# Sheet1.net
KiCad netlist of a schematic drawn in Altium Designer
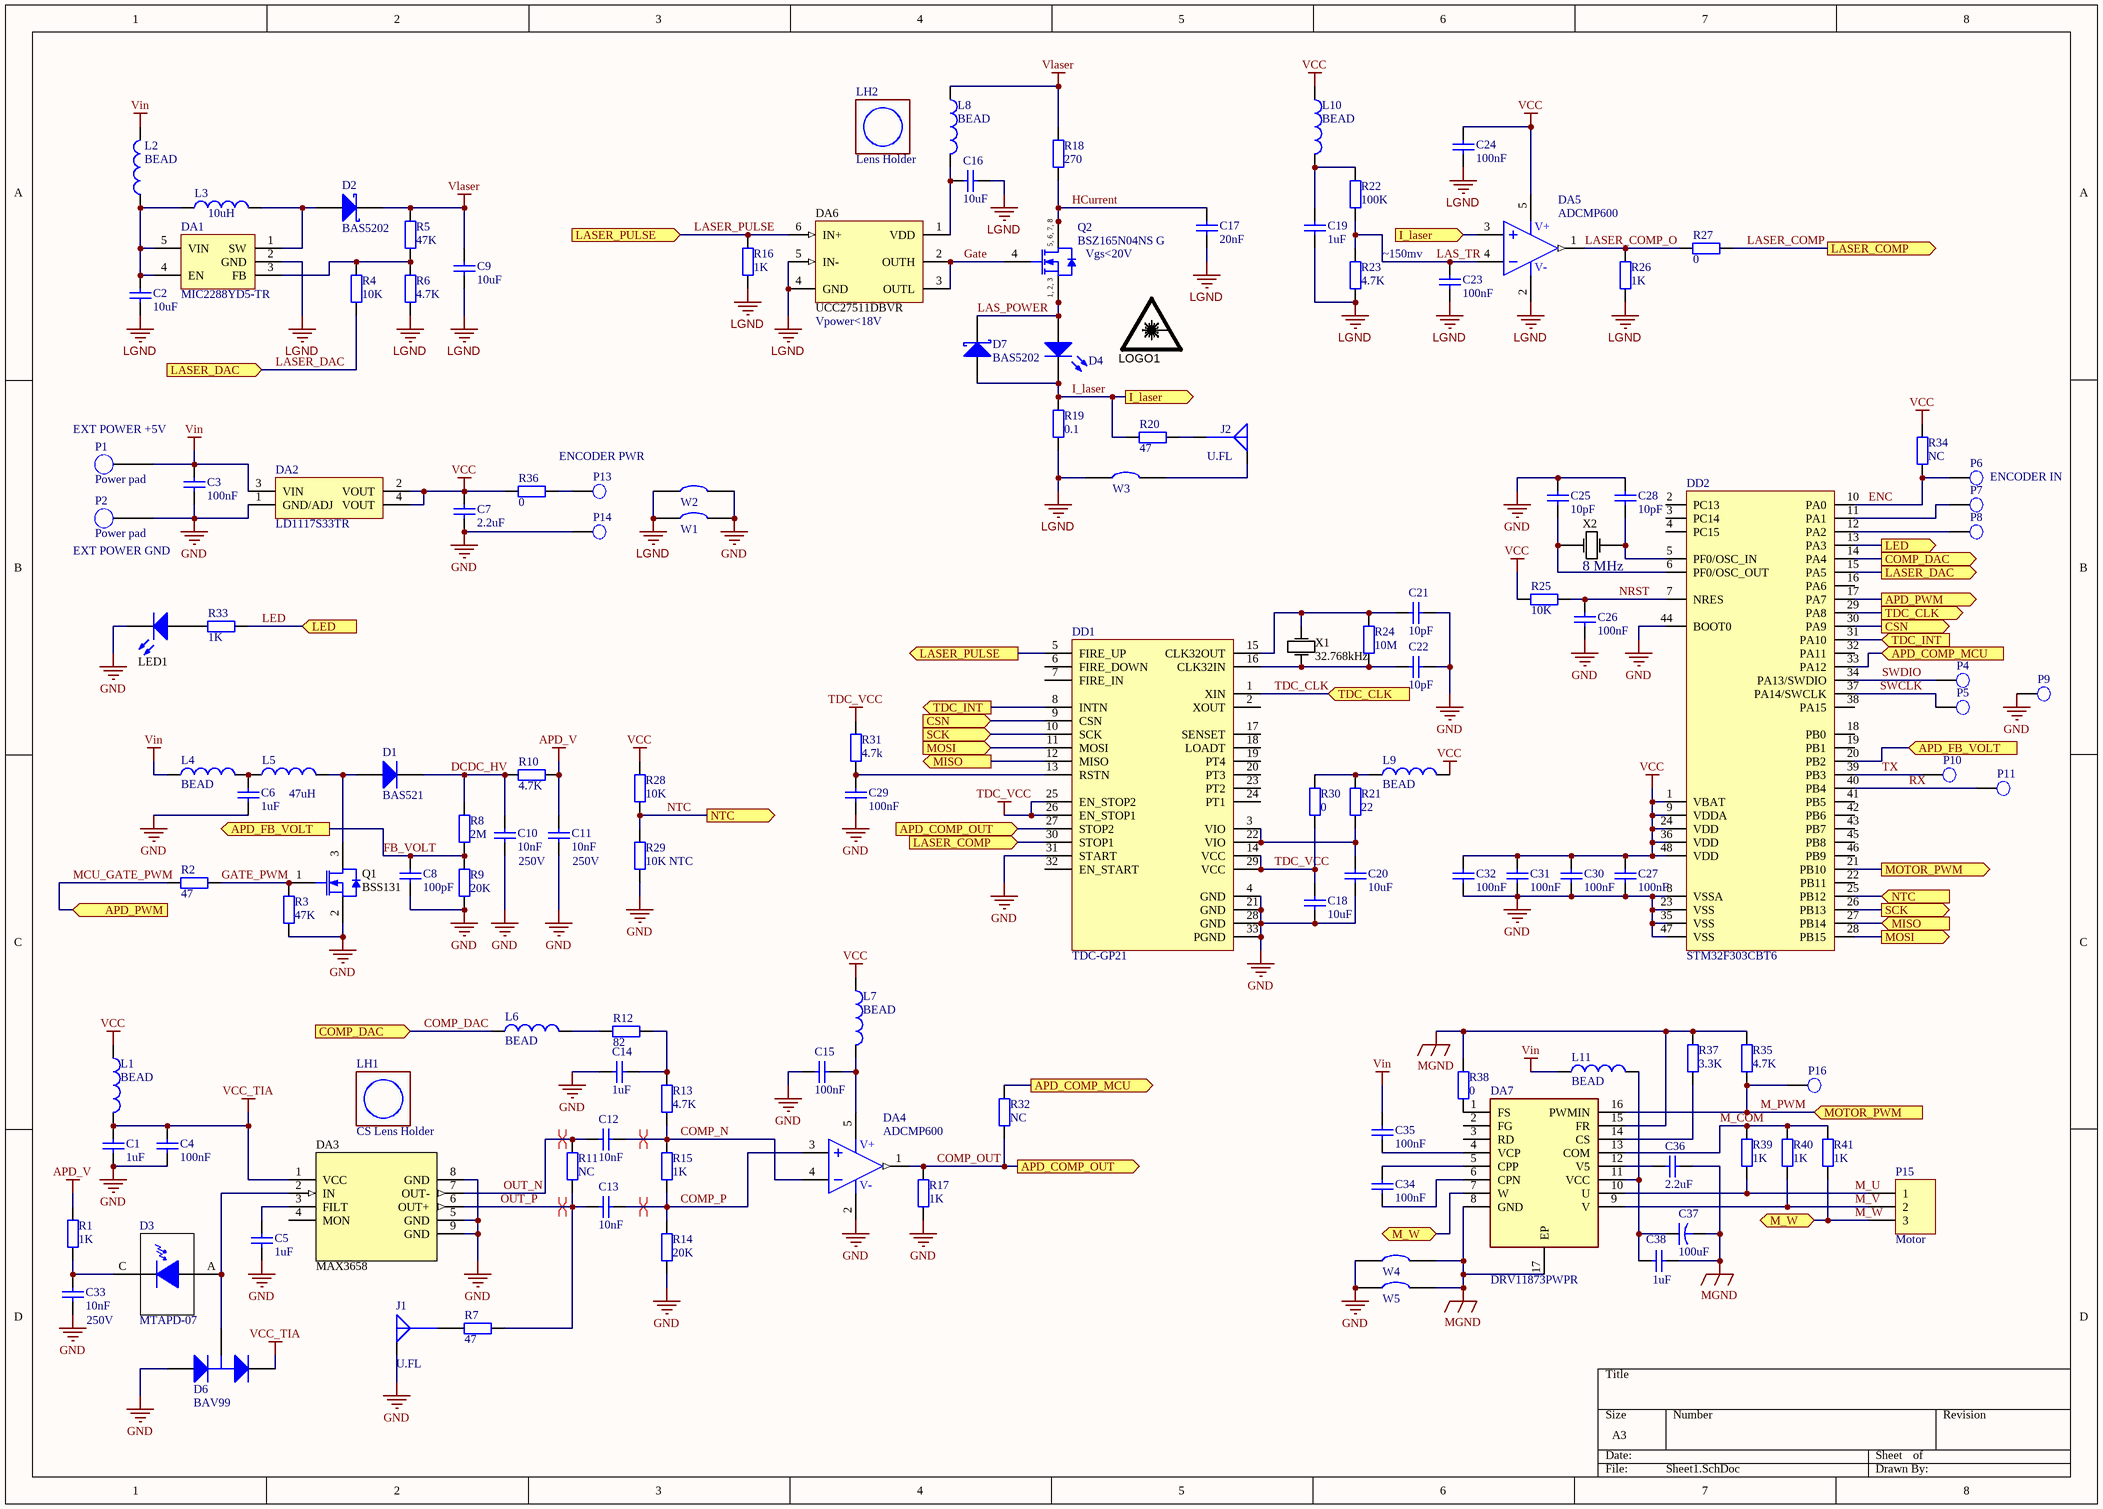
[diagram p0: Sheet1.SchDoc]

(export (version "E")
  (design (tool "Eeschema 10.0.6"))
  (components
    (comp (ref "C1")
      (value "1uF")
      (footprint "CAPC2012X135N")
      (description "Chip capacitor")
      (fields (field (name "VOLTAGE") "25V"))
      (libsource (lib "MyLibSch") (part "CC0805"))
    )
    (comp (ref "C2")
      (value "10uF")
      (footprint "CAPC1608X90N")
      (description "Chip capacitor")
      (fields (field (name "VOLTAGE") "25V"))
      (libsource (lib "MyLibSch") (part "CC0805"))
    )
    (comp (ref "C3")
      (value "100nF")
      (footprint "CAPC1608X90N")
      (description "Chip capacitor")
      (fields (field (name "VOLTAGE") "25V"))
      (libsource (lib "MyLibSch") (part "CC0805"))
    )
    (comp (ref "C4")
      (value "100nF")
      (footprint "CAPC1608X90N")
      (description "Chip capacitor")
      (fields (field (name "VOLTAGE") "25V"))
      (libsource (lib "MyLibSch") (part "CC0805"))
    )
    (comp (ref "C5")
      (value "1uF")
      (footprint "CAPC2012X135N")
      (description "Chip capacitor")
      (fields (field (name "VOLTAGE") "25V"))
      (libsource (lib "MyLibSch") (part "CC0805"))
    )
    (comp (ref "C6")
      (value "1uF")
      (footprint "CAPC2012X135N")
      (description "Chip capacitor")
      (fields (field (name "VOLTAGE") "25V"))
      (libsource (lib "MyLibSch") (part "CC0805"))
    )
    (comp (ref "C7")
      (value "2.2uF")
      (footprint "CAPC1608X90N")
      (description "Chip capacitor")
      (fields (field (name "VOLTAGE") "25V"))
      (libsource (lib "MyLibSch") (part "CC0805"))
    )
    (comp (ref "C8")
      (value "100pF")
      (footprint "CAPC1608X90N")
      (description "Chip capacitor")
      (fields (field (name "VOLTAGE") "25V"))
      (libsource (lib "MyLibSch") (part "CC0805"))
    )
    (comp (ref "C9")
      (value "10uF")
      (footprint "CAPC1608X90N")
      (description "Chip capacitor")
      (fields (field (name "VOLTAGE") "50V"))
      (libsource (lib "MyLibSch") (part "CC0805"))
    )
    (comp (ref "C10")
      (value "10nF")
      (footprint "CAPC2012X135N")
      (description "Chip capacitor")
      (fields (field (name "VOLTAGE") "250V"))
      (libsource (lib "MyLibSch") (part "CC0805"))
    )
    (comp (ref "C11")
      (value "10nF")
      (footprint "CAPC2012X135N")
      (description "Chip capacitor")
      (fields (field (name "VOLTAGE") "250V"))
      (libsource (lib "MyLibSch") (part "CC0805"))
    )
    (comp (ref "C12")
      (value "10nF")
      (footprint "CAPC1608X90N")
      (description "Chip capacitor")
      (fields (field (name "VOLTAGE") "25V"))
      (libsource (lib "MyLibSch") (part "CC0805"))
    )
    (comp (ref "C13")
      (value "10nF")
      (footprint "CAPC1608X90N")
      (description "Chip capacitor")
      (fields (field (name "VOLTAGE") "25V"))
      (libsource (lib "MyLibSch") (part "CC0805"))
    )
    (comp (ref "C14")
      (value "1uF")
      (footprint "CAPC2012X135N")
      (description "Chip capacitor")
      (fields (field (name "VOLTAGE") "25V"))
      (libsource (lib "MyLibSch") (part "CC0805"))
    )
    (comp (ref "C15")
      (value "100nF")
      (footprint "CAPC1608X90N")
      (description "Chip capacitor")
      (fields (field (name "VOLTAGE") "25V"))
      (libsource (lib "MyLibSch") (part "CC0805"))
    )
    (comp (ref "C16")
      (value "10uF")
      (footprint "CAPC1608X90N")
      (description "Chip capacitor")
      (fields (field (name "VOLTAGE") "25V"))
      (libsource (lib "MyLibSch") (part "CC0805"))
    )
    (comp (ref "C17")
      (value "20nF")
      (footprint "CAPC1608X90N")
      (description "Chip capacitor")
      (fields (field (name "VOLTAGE") "50V"))
      (libsource (lib "MyLibSch") (part "CC0805"))
    )
    (comp (ref "C18")
      (value "10uF")
      (footprint "CAPC1608X90N")
      (description "Chip capacitor")
      (fields (field (name "VOLTAGE") "25V"))
      (libsource (lib "MyLibSch") (part "CC0805"))
    )
    (comp (ref "C19")
      (value "1uF")
      (footprint "CAPC1608X90N")
      (description "Chip capacitor")
      (fields (field (name "VOLTAGE") "25V"))
      (libsource (lib "MyLibSch") (part "CC0805"))
    )
    (comp (ref "C20")
      (value "10uF")
      (footprint "CAPC1608X90N")
      (description "Chip capacitor")
      (fields (field (name "VOLTAGE") "25V"))
      (libsource (lib "MyLibSch") (part "CC0805"))
    )
    (comp (ref "C21")
      (value "10pF")
      (footprint "CAPC1608X90N")
      (description "Chip capacitor")
      (fields (field (name "VOLTAGE") "25V"))
      (libsource (lib "MyLibSch") (part "CC0805"))
    )
    (comp (ref "C22")
      (value "10pF")
      (footprint "CAPC1608X90N")
      (description "Chip capacitor")
      (fields (field (name "VOLTAGE") "25V"))
      (libsource (lib "MyLibSch") (part "CC0805"))
    )
    (comp (ref "C23")
      (value "100nF")
      (footprint "CAPC1608X90N")
      (description "Chip capacitor")
      (fields (field (name "VOLTAGE") "25V"))
      (libsource (lib "MyLibSch") (part "CC0805"))
    )
    (comp (ref "C24")
      (value "100nF")
      (footprint "CAPC1608X90N")
      (description "Chip capacitor")
      (fields (field (name "VOLTAGE") "25V"))
      (libsource (lib "MyLibSch") (part "CC0805"))
    )
    (comp (ref "C25")
      (value "10pF")
      (footprint "CAPC1608X90N")
      (description "Chip capacitor")
      (fields (field (name "VOLTAGE") "25V"))
      (libsource (lib "MyLibSch") (part "CC0805"))
    )
    (comp (ref "C26")
      (value "100nF")
      (footprint "CAPC1608X90N")
      (description "Chip capacitor")
      (fields (field (name "VOLTAGE") "25V"))
      (libsource (lib "MyLibSch") (part "CC0805"))
    )
    (comp (ref "C27")
      (value "100nF")
      (footprint "CAPC1608X90N")
      (description "Chip capacitor")
      (fields (field (name "VOLTAGE") "25V"))
      (libsource (lib "MyLibSch") (part "CC0805"))
    )
    (comp (ref "C28")
      (value "10pF")
      (footprint "CAPC1608X90N")
      (description "Chip capacitor")
      (fields (field (name "VOLTAGE") "25V"))
      (libsource (lib "MyLibSch") (part "CC0805"))
    )
    (comp (ref "C29")
      (value "100nF")
      (footprint "CAPC1608X90N")
      (description "Chip capacitor")
      (fields (field (name "VOLTAGE") "25V"))
      (libsource (lib "MyLibSch") (part "CC0805"))
    )
    (comp (ref "C30")
      (value "100nF")
      (footprint "CAPC1608X90N")
      (description "Chip capacitor")
      (fields (field (name "VOLTAGE") "25V"))
      (libsource (lib "MyLibSch") (part "CC0805"))
    )
    (comp (ref "C31")
      (value "100nF")
      (footprint "CAPC1608X90N")
      (description "Chip capacitor")
      (fields (field (name "VOLTAGE") "25V"))
      (libsource (lib "MyLibSch") (part "CC0805"))
    )
    (comp (ref "C32")
      (value "100nF")
      (footprint "CAPC1608X90N")
      (description "Chip capacitor")
      (fields (field (name "VOLTAGE") "25V"))
      (libsource (lib "MyLibSch") (part "CC0805"))
    )
    (comp (ref "C33")
      (value "10nF")
      (footprint "CAPC2012X135N")
      (description "Chip capacitor")
      (fields (field (name "VOLTAGE") "250V"))
      (libsource (lib "MyLibSch") (part "CC0805"))
    )
    (comp (ref "C34")
      (value "100nF")
      (footprint "CAPC1608X90N")
      (description "Chip capacitor")
      (fields (field (name "VOLTAGE") "25V"))
      (libsource (lib "MyLibSch") (part "CC0805"))
    )
    (comp (ref "C35")
      (value "100nF")
      (footprint "CAPC1608X90N")
      (description "Chip capacitor")
      (fields (field (name "VOLTAGE") "25V"))
      (libsource (lib "MyLibSch") (part "CC0805"))
    )
    (comp (ref "C36")
      (value "2.2uF")
      (footprint "CAPC1608X90N")
      (description "Chip capacitor")
      (fields (field (name "VOLTAGE") "25V"))
      (libsource (lib "MyLibSch") (part "CC0805"))
    )
    (comp (ref "C37")
      (value "100uF")
      (footprint "CAPR5-4X5")
      (description "Capacitor")
      (fields (field (name "Comment") "Cap2") (field (name "PUBLISHER") "Altium Limited"))
      (libsource (lib "Miscellaneous Devices") (part "Cap2"))
    )
    (comp (ref "C38")
      (value "1uF")
      (footprint "CAPC1608X90N")
      (description "Chip capacitor")
      (fields (field (name "VOLTAGE") "25V"))
      (libsource (lib "MyLibSch") (part "CC0805"))
    )
    (comp (ref "D1") (value "BAS521") (footprint "SOD523F") (libsource (lib "MyLibSch") (part "DIODE 2 pin")))
    (comp (ref "D2")
      (value "BAS5202")
      (footprint "SOD523F")
      (description "Schottky Diode")
      (fields (field (name "PUBLISHER") "Altium Limited"))
      (libsource (lib "Miscellaneous Devices") (part "D Schottky"))
    )
    (comp (ref "D3")
      (value "MTAPD-07")
      (footprint "LCC3")
      (description "APD photodiode")
      (libsource (lib "lcd_lib") (part "MTAPD-07"))
    )
    (comp (ref "D4")
      (value "Laser SPL PL90_3")
      (footprint "SPL_PL90")
      (description "TO-18 Laser")
      (libsource (lib "lcd_lib") (part "TO-18 Laser"))
    )
    (comp (ref "D6")
      (value "BAV99")
      (footprint "SOT-23")
      (description "Silicon Switching Diode Array for High-Speed Switching")
      (fields (field (name "PUBLISHER") "Altium Limited"))
      (libsource (lib "Infineon Discrete Diode") (part "BAV99"))
    )
    (comp (ref "D7")
      (value "BAS5202")
      (footprint "SOD523F")
      (description "Schottky Diode")
      (fields (field (name "PUBLISHER") "Altium Limited"))
      (libsource (lib "Miscellaneous Devices") (part "D Schottky"))
    )
    (comp (ref "DA1")
      (value "MIC2288YD5-TR")
      (footprint "SOT23-5")
      (description "Step Up")
      (libsource (lib "lcd_lib") (part "MIC2288"))
    )
    (comp (ref "DA2")
      (value "LD1117S33TR")
      (footprint "SOT223")
      (description "LOW DROP FIXED AND ADJUSTABLE  POSITIVE VOLTAGE REGULATORS")
      (libsource (lib "MyLibSch") (part "LD1117S"))
    )
    (comp (ref "DA3")
      (value "MAX3658")
      (footprint "TDFN-8_0.65")
      (description "Transimpedance Amplifier")
      (fields (field (name "PART NUMBER") "AD7278"))
      (libsource (lib "lcd_lib") (part "MAX3658"))
    )
    (comp (ref "DA4")
      (value "ADCMP600")
      (footprint "SOT23-5")
      (description "Fast comparator")
      (libsource (lib "lcd_lib") (part "ADCMP600"))
    )
    (comp (ref "DA5")
      (value "ADCMP600")
      (footprint "SOT23-5")
      (description "Fast comparator")
      (libsource (lib "lcd_lib") (part "ADCMP600"))
    )
    (comp (ref "DA6")
      (value "UCC27511DBVR")
      (footprint "Miscellaneous Devices:SOT23-6_M")
      (description "Single-Channel High-Speed Low-Side Gate Driver (with 4-A Peak Source and 8-A Peak Sink), DBV0006A")
      (fields
        (field (name "ALTERNATE PARTNUMBER") "UCC27511DBVT")
        (field (name "MANUFACTURER") "Texas Instruments")
        (field (name "SYMBOLCREATOR") "a0411947")
        (field (name "PUBLISHER") "Texas Instruments")
      )
      (libsource (lib "TI_Pre_Release") (part "UCC27511DBVR"))
    )
    (comp (ref "DA7")
      (value "DRV11873PWPR")
      (footprint "SamacSys:SOP65P640X120-17N")
      (description "Integrated Circuit")
      (fields
        (field (name "MOUSER PART NUMBER") "595-DRV11873PWPR")
        (field (name "RS PART NUMBER") "8136444P")
      )
      (libsource (lib "*") (part "DRV11873PWPR"))
    )
    (comp (ref "DD1")
      (value "TDC-GP21")
      (footprint "QFN32 5x5mm")
      (description "TDC")
      (libsource (lib "lcd_lib") (part "TDC_GP21"))
    )
    (comp (ref "DD2")
      (value "STM32F303CBT6")
      (footprint "LQFP-48_N")
      (description "Microcontroller")
      (libsource (lib "lcd_lib") (part "STM32F3_LQFP48"))
    )
    (comp (ref "J1")
      (value "U.FL")
      (footprint "TE C-1909763")
      (description "U.FL Connector")
      (libsource (lib "RF Connector") (part "RF Connector - SMA"))
    )
    (comp (ref "J2")
      (value "U.FL")
      (footprint "TE C-1909763")
      (description "U.FL Connector")
      (libsource (lib "RF Connector") (part "RF Connector - SMA"))
    )
    (comp (ref "L1")
      (value "BEAD")
      (footprint "INDC1608N")
      (description "Ferrit Bead")
      (libsource (lib "MyLibSch") (part "BEAD"))
    )
    (comp (ref "L2")
      (value "BEAD")
      (footprint "INDC1608N")
      (description "Ferrit Bead")
      (libsource (lib "MyLibSch") (part "BEAD"))
    )
    (comp (ref "L3")
      (value "10uH")
      (footprint "MyLibPcb:V0805HD")
      (description "Inductor")
      (fields (field (name "PUBLISHER") "Altium Limited"))
      (libsource (lib "Miscellaneous Devices") (part "Inductor"))
    )
    (comp (ref "L4")
      (value "BEAD")
      (footprint "INDC1608N")
      (description "Ferrit Bead")
      (libsource (lib "MyLibSch") (part "BEAD"))
    )
    (comp (ref "L5")
      (value "47uH")
      (footprint "INDC3216")
      (description "Inductor")
      (fields (field (name "PUBLISHER") "Altium Limited"))
      (libsource (lib "Miscellaneous Devices") (part "Inductor"))
    )
    (comp (ref "L6")
      (value "BEAD")
      (footprint "INDC1608N")
      (description "Ferrit Bead")
      (libsource (lib "MyLibSch") (part "BEAD"))
    )
    (comp (ref "L7")
      (value "BEAD")
      (footprint "INDC1608N")
      (description "Ferrit Bead")
      (libsource (lib "MyLibSch") (part "BEAD"))
    )
    (comp (ref "L8")
      (value "BEAD")
      (footprint "INDC1608N")
      (description "Ferrit Bead")
      (libsource (lib "MyLibSch") (part "BEAD"))
    )
    (comp (ref "L9")
      (value "BEAD")
      (footprint "INDC1608N")
      (description "Ferrit Bead")
      (libsource (lib "MyLibSch") (part "BEAD"))
    )
    (comp (ref "L10")
      (value "BEAD")
      (footprint "INDC1608N")
      (description "Ferrit Bead")
      (libsource (lib "MyLibSch") (part "BEAD"))
    )
    (comp (ref "L11")
      (value "BEAD")
      (footprint "INDC1608N")
      (description "Ferrit Bead")
      (libsource (lib "MyLibSch") (part "BEAD"))
    )
    (comp (ref "LED1")
      (value "LED")
      (footprint "PcbLib3:LED_0603")
      (description "LED_0603")
      (libsource (lib "lcd_lib") (part "LED_0603"))
    )
    (comp (ref "LH1")
      (value "CS Lens Holder")
      (footprint "Lens Holder CS")
      (libsource (lib "lcd_lib") (part "CS Lens Holder"))
    )
    (comp (ref "LH2")
      (value "Lens Holder")
      (footprint "LENS_HOLDER_20MM_ADJ")
      (description "M12 Lens Holder")
      (libsource (lib "lcd_lib") (part "M12 Lens Holder"))
    )
    (comp (ref "LOGO1")
      (value "LASER RADIATION")
      (footprint "LaserWarning_Small")
      (description "Laser Warning Symbol")
      (fields (field (name "SYMBOLCREATOR") "a0412235") (field (name "PUBLISHER") "Texas Instruments"))
      (libsource (lib "Logos") (part "Laser_Warning"))
    )
    (comp (ref "P1")
      (value "Power pad")
      (footprint "Ext_power_pad")
      (description "Pad for wire")
      (libsource (lib "lcd_lib") (part "Power_pad"))
    )
    (comp (ref "P2")
      (value "Power pad")
      (footprint "Ext_power_pad")
      (description "Pad for wire")
      (libsource (lib "lcd_lib") (part "Power_pad"))
    )
    (comp (ref "P4")
      (value "Pad")
      (footprint "PcbLib3:Ext_pad_2")
      (description "Pad for wire")
      (libsource (lib "lcd_lib") (part "Ext Pad"))
    )
    (comp (ref "P5")
      (value "Pad")
      (footprint "PcbLib3:Ext_pad_2")
      (description "Pad for wire")
      (libsource (lib "lcd_lib") (part "Ext Pad"))
    )
    (comp (ref "P6")
      (value "Pad")
      (footprint "Ext_hole")
      (description "Pad for wire")
      (libsource (lib "lcd_lib") (part "Ext Pad"))
    )
    (comp (ref "P7")
      (value "Pad")
      (footprint "PcbLib3:Ext_pad_2")
      (description "Pad for wire")
      (libsource (lib "lcd_lib") (part "Ext Pad"))
    )
    (comp (ref "P8")
      (value "Pad")
      (footprint "PcbLib3:Ext_pad_2")
      (description "Pad for wire")
      (libsource (lib "lcd_lib") (part "Ext Pad"))
    )
    (comp (ref "P9")
      (value "Pad")
      (footprint "PcbLib3:Ext_pad_2")
      (description "Pad for wire")
      (libsource (lib "lcd_lib") (part "Ext Pad"))
    )
    (comp (ref "P10")
      (value "Pad")
      (footprint "PcbLib3:Ext_pad_2")
      (description "Pad for wire")
      (libsource (lib "lcd_lib") (part "Ext Pad"))
    )
    (comp (ref "P11")
      (value "Pad")
      (footprint "PcbLib3:Ext_pad_2")
      (description "Pad for wire")
      (libsource (lib "lcd_lib") (part "Ext Pad"))
    )
    (comp (ref "P13")
      (value "Pad")
      (footprint "Ext_hole")
      (description "Pad for wire")
      (libsource (lib "lcd_lib") (part "Ext Pad"))
    )
    (comp (ref "P14")
      (value "Pad")
      (footprint "Ext_hole")
      (description "Pad for wire")
      (libsource (lib "lcd_lib") (part "Ext Pad"))
    )
    (comp (ref "P15")
      (value "Motor")
      (footprint "HDR1X3")
      (description "Header, 3-Pin")
      (fields (field (name "PUBLISHER") "Altium Limited"))
      (libsource (lib "Miscellaneous Connectors") (part "Header 3"))
    )
    (comp (ref "P16")
      (value "Pad")
      (footprint "Ext_pad_small")
      (description "Pad for wire")
      (libsource (lib "lcd_lib") (part "Ext Pad"))
    )
    (comp (ref "Q1")
      (value "BSS131")
      (footprint "INF-PG-SOT23_N")
      (fields (field (name "MANUFACTURER") "Infineon"))
      (libsource (lib "altium-import") (part "root_0_BSS131_"))
    )
    (comp (ref "Q2")
      (value "BSZ165N04NS G")
      (footprint "INF-PG-TSDSON-8-1_A_V")
      (fields (field (name "MANUFACTURER") "Infineon"))
      (libsource (lib "BSZ165N04NS G") (part "BSZ165N04NS G"))
    )
    (comp (ref "R1")
      (value "1K")
      (footprint "RESC1608X55N")
      (description "Chip resistor")
      (fields (field (name "TOLERANCE") "5%"))
      (libsource (lib "MyLibSch") (part "RC0805"))
    )
    (comp (ref "R2")
      (value "47")
      (footprint "RESC1608X55N")
      (description "Chip resistor")
      (fields (field (name "TOLERANCE") "5%"))
      (libsource (lib "") (part "RC0805_1"))
    )
    (comp (ref "R3")
      (value "47K")
      (footprint "RESC1608X55N")
      (description "Chip resistor")
      (fields (field (name "TOLERANCE") "5%"))
      (libsource (lib "") (part "RC0805_3"))
    )
    (comp (ref "R4")
      (value "10K")
      (footprint "RESC1608X55N")
      (description "Chip resistor")
      (fields (field (name "TOLERANCE") "5%"))
      (libsource (lib "MyLibSch") (part "RC0805"))
    )
    (comp (ref "R5")
      (value "47K")
      (footprint "RESC1608X55N")
      (description "Chip resistor")
      (fields (field (name "TOLERANCE") "5%"))
      (libsource (lib "MyLibSch") (part "RC0805"))
    )
    (comp (ref "R6")
      (value "4.7K")
      (footprint "RESC1608X55N")
      (description "Chip resistor")
      (fields (field (name "TOLERANCE") "5%"))
      (libsource (lib "MyLibSch") (part "RC0805"))
    )
    (comp (ref "R7")
      (value "47")
      (footprint "RESC1608X55N")
      (description "Chip resistor")
      (fields (field (name "TOLERANCE") "5%"))
      (libsource (lib "MyLibSch") (part "RC0805"))
    )
    (comp (ref "R8")
      (value "2M")
      (footprint "RESC2012X70N")
      (description "Chip resistor")
      (fields (field (name "TOLERANCE") "5%"))
      (libsource (lib "MyLibSch") (part "RC0805"))
    )
    (comp (ref "R9")
      (value "20K")
      (footprint "RESC1608X55N")
      (description "Chip resistor")
      (fields (field (name "TOLERANCE") "5%"))
      (libsource (lib "") (part "RC0805_3"))
    )
    (comp (ref "R10")
      (value "4.7K")
      (footprint "RESC1608X55N")
      (description "Chip resistor")
      (fields (field (name "TOLERANCE") "5%"))
      (libsource (lib "") (part "RC0805_2"))
    )
    (comp (ref "R11")
      (value "NC")
      (footprint "RESC1608X55N")
      (description "Chip resistor")
      (fields (field (name "TOLERANCE") "5%"))
      (libsource (lib "MyLibSch") (part "RC0805"))
    )
    (comp (ref "R12")
      (value "82")
      (footprint "RESC1608X55N")
      (description "Chip resistor")
      (fields (field (name "TOLERANCE") "5%"))
      (libsource (lib "") (part "RC0805_2"))
    )
    (comp (ref "R13")
      (value "4.7K")
      (footprint "RESC1608X55N")
      (description "Chip resistor")
      (fields (field (name "TOLERANCE") "5%"))
      (libsource (lib "MyLibSch") (part "RC0805"))
    )
    (comp (ref "R14")
      (value "20K")
      (footprint "RESC2012X70N")
      (description "Chip resistor")
      (fields (field (name "TOLERANCE") "5%"))
      (libsource (lib "MyLibSch") (part "RC0805"))
    )
    (comp (ref "R15")
      (value "1K")
      (footprint "RESC1608X55N")
      (description "Chip resistor")
      (fields (field (name "TOLERANCE") "5%"))
      (libsource (lib "MyLibSch") (part "RC0805"))
    )
    (comp (ref "R16")
      (value "1K")
      (footprint "RESC1608X55N")
      (description "Chip resistor")
      (fields (field (name "TOLERANCE") "5%"))
      (libsource (lib "MyLibSch") (part "RC0805"))
    )
    (comp (ref "R17")
      (value "1K")
      (footprint "RESC1608X55N")
      (description "Chip resistor")
      (fields (field (name "TOLERANCE") "5%"))
      (libsource (lib "MyLibSch") (part "RC0805"))
    )
    (comp (ref "R18")
      (value "270")
      (footprint "RESC1608X55N")
      (description "Chip resistor")
      (fields (field (name "TOLERANCE") "5%"))
      (libsource (lib "MyLibSch") (part "RC0805"))
    )
    (comp (ref "R19")
      (value "0.1")
      (footprint "RESC2012X70N")
      (description "Chip resistor")
      (fields (field (name "TOLERANCE") "5%"))
      (libsource (lib "MyLibSch") (part "RC0805"))
    )
    (comp (ref "R20")
      (value "47")
      (footprint "RESC1608X55N")
      (description "Chip resistor")
      (fields (field (name "TOLERANCE") "5%"))
      (libsource (lib "") (part "RC0805_2"))
    )
    (comp (ref "R21")
      (value "22")
      (footprint "RESC1608X55N")
      (description "Chip resistor")
      (fields (field (name "TOLERANCE") "5%"))
      (libsource (lib "") (part "RC0805_3"))
    )
    (comp (ref "R22")
      (value "100K")
      (footprint "RESC1608X55N")
      (description "Chip resistor")
      (fields (field (name "TOLERANCE") "5%"))
      (libsource (lib "") (part "RC0805_3"))
    )
    (comp (ref "R23")
      (value "4.7K")
      (footprint "RESC1608X55N")
      (description "Chip resistor")
      (fields (field (name "TOLERANCE") "5%"))
      (libsource (lib "") (part "RC0805_3"))
    )
    (comp (ref "R24")
      (value "10M")
      (footprint "RESC1608X55N")
      (description "Chip resistor")
      (fields (field (name "TOLERANCE") "5%"))
      (libsource (lib "MyLibSch") (part "RC0805"))
    )
    (comp (ref "R25")
      (value "10K")
      (footprint "RESC1608X55N")
      (description "Chip resistor")
      (fields (field (name "TOLERANCE") "5%"))
      (libsource (lib "") (part "RC0805_1"))
    )
    (comp (ref "R26")
      (value "1K")
      (footprint "RESC1608X55N")
      (description "Chip resistor")
      (fields (field (name "TOLERANCE") "5%"))
      (libsource (lib "MyLibSch") (part "RC0805"))
    )
    (comp (ref "R27")
      (value "0")
      (footprint "RESC1608X55N")
      (description "Chip resistor")
      (fields (field (name "TOLERANCE") "5%"))
      (libsource (lib "") (part "RC0805_1"))
    )
    (comp (ref "R28")
      (value "10K")
      (footprint "RESC1608X55N")
      (description "Chip resistor")
      (fields (field (name "TOLERANCE") "5%"))
      (libsource (lib "") (part "RC0805_3"))
    )
    (comp (ref "R29")
      (value "10K NTC")
      (footprint "RESC1608X55N")
      (description "Chip resistor")
      (fields (field (name "TOLERANCE") "5%"))
      (libsource (lib "MyLibSch") (part "RC0805"))
    )
    (comp (ref "R30")
      (value "0")
      (footprint "RESC1608X55N")
      (description "Chip resistor")
      (fields (field (name "TOLERANCE") "5%"))
      (libsource (lib "") (part "RC0805_3"))
    )
    (comp (ref "R31")
      (value "4.7k")
      (footprint "RESC1608X55N")
      (description "Chip resistor")
      (fields (field (name "TOLERANCE") "5%"))
      (libsource (lib "") (part "RC0805_3"))
    )
    (comp (ref "R32")
      (value "NC")
      (footprint "RESC1608X55N")
      (description "Chip resistor")
      (fields (field (name "TOLERANCE") "5%"))
      (libsource (lib "") (part "RC0805_3"))
    )
    (comp (ref "R33")
      (value "1K")
      (footprint "RESC1608X55N")
      (description "Chip resistor")
      (fields (field (name "TOLERANCE") "5%"))
      (libsource (lib "") (part "RC0805_1"))
    )
    (comp (ref "R34")
      (value "NC")
      (footprint "RESC1608X55N")
      (description "Chip resistor")
      (fields (field (name "TOLERANCE") "5%"))
      (libsource (lib "") (part "RC0805_3"))
    )
    (comp (ref "R35")
      (value "4.7K")
      (footprint "RESC1608X55N")
      (description "Chip resistor")
      (fields (field (name "TOLERANCE") "5%"))
      (libsource (lib "MyLibSch") (part "RC0805"))
    )
    (comp (ref "R36")
      (value "0")
      (footprint "RESC1608X55N")
      (description "Chip resistor")
      (fields (field (name "TOLERANCE") "5%"))
      (libsource (lib "") (part "RC0805_1"))
    )
    (comp (ref "R37")
      (value "3.3K")
      (footprint "RESC1608X55N")
      (description "Chip resistor")
      (fields (field (name "TOLERANCE") "5%"))
      (libsource (lib "MyLibSch") (part "RC0805"))
    )
    (comp (ref "R38")
      (value "0")
      (footprint "RESC1608X55N")
      (description "Chip resistor")
      (fields (field (name "TOLERANCE") "5%"))
      (libsource (lib "MyLibSch") (part "RC0805"))
    )
    (comp (ref "R39")
      (value "1K")
      (footprint "RESC1608X55N")
      (description "Chip resistor")
      (fields (field (name "TOLERANCE") "5%"))
      (libsource (lib "MyLibSch") (part "RC0805"))
    )
    (comp (ref "R40")
      (value "1K")
      (footprint "RESC1608X55N")
      (description "Chip resistor")
      (fields (field (name "TOLERANCE") "5%"))
      (libsource (lib "MyLibSch") (part "RC0805"))
    )
    (comp (ref "R41")
      (value "1K")
      (footprint "RESC1608X55N")
      (description "Chip resistor")
      (fields (field (name "TOLERANCE") "5%"))
      (libsource (lib "MyLibSch") (part "RC0805"))
    )
    (comp (ref "W1")
      (value "NET connector")
      (footprint "Net connector")
      (libsource (lib "lcd_lib") (part "NET connector"))
    )
    (comp (ref "W2")
      (value "NET connector")
      (footprint "Net connector")
      (libsource (lib "lcd_lib") (part "NET connector"))
    )
    (comp (ref "W3")
      (value "NET connector")
      (footprint "Net connector2")
      (libsource (lib "lcd_lib") (part "NET connector"))
    )
    (comp (ref "W4")
      (value "NET connector")
      (footprint "Net connector")
      (libsource (lib "lcd_lib") (part "NET connector"))
    )
    (comp (ref "W5")
      (value "NET connector")
      (footprint "Net connector")
      (libsource (lib "lcd_lib") (part "NET connector"))
    )
    (comp (ref "X1")
      (value "32.768kHz")
      (footprint "QUARTZ_32K")
      (description "Quartz")
      (libsource (lib "lcd_lib") (part "Quartz_32k"))
    )
    (comp (ref "X2")
      (value "8 MHz")
      (footprint "SX-6 QUARTZ")
      (description "Quartz_SX-6 (SMD06035C4)")
      (fields (field (name "Comment") "Quartz"))
      (libsource (lib "lcd_lib") (part "Quartz_SX-6"))
    )
  )
  (nets
    (net (code "1") (name "/APD_COMP_MCU") (class "Default")
      (node (ref "DD2") (pin "33") (pinfunction "PA12_33") (pintype "passive"))
      (node (ref "R32") (pin "1") (pinfunction "1_1") (pintype "passive"))
    )
    (net (code "2") (name "/COMP_DAC") (class "Default")
      (node (ref "DD2") (pin "14") (pinfunction "PA4_14") (pintype "passive"))
      (node (ref "L6") (pin "1") (pinfunction "1_1") (pintype "passive"))
    )
    (net (code "3") (name "/COMP_N") (class "Default")
      (node (ref "C12") (pin "1") (pinfunction "1_1") (pintype "passive"))
      (node (ref "DA4") (pin "4") (pinfunction "IN-_4") (pintype "passive"))
      (node (ref "R13") (pin "1") (pinfunction "1_1") (pintype "passive"))
      (node (ref "R15") (pin "2") (pinfunction "2_2") (pintype "passive"))
    )
    (net (code "4") (name "/COMP_OUT") (class "Default")
      (node (ref "DA4") (pin "1") (pinfunction "OUT_1") (pintype "output"))
      (node (ref "DD1") (pin "27") (pinfunction "STOP2_27") (pintype "passive"))
      (node (ref "R17") (pin "2") (pinfunction "2_2") (pintype "passive"))
      (node (ref "R32") (pin "2") (pinfunction "2_2") (pintype "passive"))
    )
    (net (code "5") (name "/COMP_P") (class "Default")
      (node (ref "C13") (pin "1") (pinfunction "1_1") (pintype "passive"))
      (node (ref "DA4") (pin "3") (pinfunction "IN+_3") (pintype "passive"))
      (node (ref "R14") (pin "2") (pinfunction "2_2") (pintype "passive"))
      (node (ref "R15") (pin "1") (pinfunction "1_1") (pintype "passive"))
    )
    (net (code "6") (name "/CSN") (class "Default")
      (node (ref "DD1") (pin "9") (pinfunction "CSN_9") (pintype "passive"))
      (node (ref "DD2") (pin "30") (pinfunction "PA9_30") (pintype "passive"))
    )
    (net (code "7") (name "/DCDC_HV") (class "Default")
      (node (ref "C10") (pin "2") (pinfunction "2_2") (pintype "passive"))
      (node (ref "D1") (pin "K") (pinfunction "K_K") (pintype "passive"))
      (node (ref "R10") (pin "2") (pinfunction "2_2") (pintype "passive"))
      (node (ref "R8") (pin "2") (pinfunction "2_2") (pintype "passive"))
    )
    (net (code "8") (name "/ENC") (class "Default")
      (node (ref "DD2") (pin "10") (pinfunction "PA0_10") (pintype "passive"))
      (node (ref "P6") (pin "1") (pinfunction "Pad_1") (pintype "passive"))
      (node (ref "R34") (pin "2") (pinfunction "2_2") (pintype "passive"))
    )
    (net (code "9") (name "/FB_VOLT") (class "Default")
      (node (ref "C8") (pin "1") (pinfunction "1_1") (pintype "passive"))
      (node (ref "DD2") (pin "20") (pinfunction "PB2_20") (pintype "passive"))
      (node (ref "R8") (pin "1") (pinfunction "1_1") (pintype "passive"))
      (node (ref "R9") (pin "1") (pinfunction "1_1") (pintype "passive"))
    )
    (net (code "10") (name "/GATE_PWM") (class "Default")
      (node (ref "Q1") (pin "1") (pinfunction "GATE_1") (pintype "passive"))
      (node (ref "R2") (pin "2") (pinfunction "2_2") (pintype "passive"))
      (node (ref "R3") (pin "1") (pinfunction "1_1") (pintype "passive"))
    )
    (net (code "11") (name "/Gate") (class "Default")
      (node (ref "DA6") (pin "2") (pinfunction "OUTH_2") (pintype "power_in"))
      (node (ref "DA6") (pin "3") (pinfunction "OUTL_3") (pintype "power_in"))
      (node (ref "Q2") (pin "4") (pinfunction "GATE_4") (pintype "passive"))
    )
    (net (code "12") (name "/HCurrent") (class "Default")
      (node (ref "C17") (pin "2") (pinfunction "2_2") (pintype "passive"))
      (node (ref "Q2") (pin "5") (pinfunction "DRAIN_5") (pintype "passive"))
      (node (ref "Q2") (pin "6") (pinfunction "DRAIN_6") (pintype "passive"))
      (node (ref "Q2") (pin "7") (pinfunction "DRAIN_7") (pintype "passive"))
      (node (ref "Q2") (pin "8") (pinfunction "DRAIN_8") (pintype "passive"))
      (node (ref "R18") (pin "1") (pinfunction "1_1") (pintype "passive"))
    )
    (net (code "13") (name "/I_laser") (class "Default")
      (node (ref "D4") (pin "K") (pinfunction "K_K") (pintype "passive"))
      (node (ref "D7") (pin "A") (pinfunction "A_A") (pintype "passive"))
      (node (ref "DA5") (pin "3") (pinfunction "IN+_3") (pintype "passive"))
      (node (ref "R19") (pin "2") (pinfunction "2_2") (pintype "passive"))
      (node (ref "R20") (pin "2") (pinfunction "2_2") (pintype "passive"))
    )
    (net (code "14") (name "/LASER_COMP") (class "Default")
      (node (ref "DD1") (pin "30") (pinfunction "STOP1_30") (pintype "passive"))
      (node (ref "R27") (pin "2") (pinfunction "2_2") (pintype "passive"))
    )
    (net (code "15") (name "/LASER_COMP_O") (class "Default")
      (node (ref "DA5") (pin "1") (pinfunction "OUT_1") (pintype "output"))
      (node (ref "R26") (pin "2") (pinfunction "2_2") (pintype "passive"))
      (node (ref "R27") (pin "1") (pinfunction "1_1") (pintype "passive"))
    )
    (net (code "16") (name "/LASER_DAC") (class "Default")
      (node (ref "DD2") (pin "15") (pinfunction "PA5_15") (pintype "passive"))
      (node (ref "R4") (pin "1") (pinfunction "1_1") (pintype "passive"))
    )
    (net (code "17") (name "/LASER_PULSE") (class "Default")
      (node (ref "DA6") (pin "6") (pinfunction "IN+_6") (pintype "input"))
      (node (ref "DD1") (pin "5") (pinfunction "FIRE_UP_5") (pintype "passive"))
      (node (ref "R16") (pin "2") (pinfunction "2_2") (pintype "passive"))
    )
    (net (code "18") (name "/LAS_POWER") (class "Default")
      (node (ref "D4") (pin "A") (pinfunction "A_A") (pintype "passive"))
      (node (ref "D7") (pin "K") (pinfunction "K_K") (pintype "passive"))
      (node (ref "Q2") (pin "1") (pinfunction "SOURCE_1") (pintype "passive"))
      (node (ref "Q2") (pin "2") (pinfunction "SOURCE_2") (pintype "passive"))
      (node (ref "Q2") (pin "3") (pinfunction "SOURCE_3") (pintype "passive"))
    )
    (net (code "19") (name "/LAS_TR") (class "Default")
      (node (ref "C23") (pin "2") (pinfunction "2_2") (pintype "passive"))
      (node (ref "DA5") (pin "4") (pinfunction "IN-_4") (pintype "passive"))
      (node (ref "R22") (pin "2") (pinfunction "2_2") (pintype "passive"))
      (node (ref "R23") (pin "1") (pinfunction "1_1") (pintype "passive"))
    )
    (net (code "20") (name "/LED") (class "Default")
      (node (ref "DD2") (pin "13") (pinfunction "PA3_13") (pintype "passive"))
      (node (ref "R33") (pin "2") (pinfunction "2_2") (pintype "passive"))
    )
    (net (code "21") (name "/MCU_GATE_PWM") (class "Default")
      (node (ref "DD2") (pin "17") (pinfunction "PA7_17") (pintype "passive"))
      (node (ref "R2") (pin "1") (pinfunction "1_1") (pintype "passive"))
    )
    (net (code "22") (name "/MISO") (class "Default")
      (node (ref "DD1") (pin "12") (pinfunction "MISO_12") (pintype "passive"))
      (node (ref "DD2") (pin "27") (pinfunction "PB14_27") (pintype "passive"))
    )
    (net (code "23") (name "/MOSI") (class "Default")
      (node (ref "DD1") (pin "11") (pinfunction "MOSI_11") (pintype "passive"))
      (node (ref "DD2") (pin "28") (pinfunction "PB15_28") (pintype "passive"))
    )
    (net (code "24") (name "/M_COM") (class "Default")
      (node (ref "DA7") (pin "13") (pinfunction "COM_13") (pintype "passive"))
      (node (ref "R39") (pin "2") (pinfunction "2_2") (pintype "passive"))
      (node (ref "R40") (pin "2") (pinfunction "2_2") (pintype "passive"))
      (node (ref "R41") (pin "2") (pinfunction "2_2") (pintype "passive"))
    )
    (net (code "25") (name "/M_PWM") (class "Default")
      (node (ref "DA7") (pin "16") (pinfunction "PWMIN_16") (pintype "passive"))
      (node (ref "DD2") (pin "21") (pinfunction "PB10_21") (pintype "passive"))
      (node (ref "P16") (pin "1") (pinfunction "Pad_1") (pintype "passive"))
      (node (ref "R35") (pin "1") (pinfunction "1_1") (pintype "passive"))
    )
    (net (code "26") (name "/M_U") (class "Default")
      (node (ref "DA7") (pin "10") (pinfunction "U_10") (pintype "passive"))
      (node (ref "P15") (pin "1") (pinfunction "1_1") (pintype "passive"))
      (node (ref "R39") (pin "1") (pinfunction "1_1") (pintype "passive"))
    )
    (net (code "27") (name "/M_V") (class "Default")
      (node (ref "DA7") (pin "9") (pinfunction "V_9") (pintype "passive"))
      (node (ref "P15") (pin "2") (pinfunction "2_2") (pintype "passive"))
      (node (ref "R40") (pin "1") (pinfunction "1_1") (pintype "passive"))
    )
    (net (code "28") (name "/M_W") (class "Default")
      (node (ref "DA7") (pin "7") (pinfunction "W_7") (pintype "passive"))
      (node (ref "P15") (pin "3") (pinfunction "3_3") (pintype "passive"))
      (node (ref "R41") (pin "1") (pinfunction "1_1") (pintype "passive"))
    )
    (net (code "29") (name "/NRST") (class "Default")
      (node (ref "C26") (pin "2") (pinfunction "2_2") (pintype "passive"))
      (node (ref "DD2") (pin "7") (pinfunction "NRES_7") (pintype "passive"))
      (node (ref "R25") (pin "2") (pinfunction "2_2") (pintype "passive"))
    )
    (net (code "30") (name "/NTC") (class "Default")
      (node (ref "DD2") (pin "25") (pinfunction "PB12_25") (pintype "passive"))
      (node (ref "R28") (pin "2") (pinfunction "2_2") (pintype "passive"))
      (node (ref "R29") (pin "2") (pinfunction "2_2") (pintype "passive"))
    )
    (net (code "31") (name "/OUT_N") (class "Default")
      (node (ref "C12") (pin "2") (pinfunction "2_2") (pintype "passive"))
      (node (ref "DA3") (pin "7") (pinfunction "OUT-_7") (pintype "output"))
      (node (ref "R11") (pin "2") (pinfunction "2_2") (pintype "passive"))
    )
    (net (code "32") (name "/OUT_P") (class "Default")
      (node (ref "C13") (pin "2") (pinfunction "2_2") (pintype "passive"))
      (node (ref "DA3") (pin "6") (pinfunction "OUT+_6") (pintype "output"))
      (node (ref "R11") (pin "1") (pinfunction "1_1") (pintype "passive"))
      (node (ref "R7") (pin "2") (pinfunction "2_2") (pintype "passive"))
    )
    (net (code "33") (name "/RX") (class "Default")
      (node (ref "DD2") (pin "40") (pinfunction "PB4_40") (pintype "passive"))
      (node (ref "P11") (pin "1") (pinfunction "Pad_1") (pintype "passive"))
    )
    (net (code "34") (name "/SCK") (class "Default")
      (node (ref "DD1") (pin "10") (pinfunction "SCK_10") (pintype "passive"))
      (node (ref "DD2") (pin "26") (pinfunction "PB13_26") (pintype "passive"))
    )
    (net (code "35") (name "/SWCLK") (class "Default")
      (node (ref "DD2") (pin "37") (pinfunction "PA14/SWCLK_37") (pintype "passive"))
      (node (ref "P5") (pin "1") (pinfunction "Pad_1") (pintype "passive"))
    )
    (net (code "36") (name "/SWDIO") (class "Default")
      (node (ref "DD2") (pin "34") (pinfunction "PA13/SWDIO_34") (pintype "passive"))
      (node (ref "P4") (pin "1") (pinfunction "Pad_1") (pintype "passive"))
    )
    (net (code "37") (name "/TDC_CLK") (class "Default")
      (node (ref "DD1") (pin "1") (pinfunction "XIN_1") (pintype "passive"))
      (node (ref "DD2") (pin "29") (pinfunction "PA8_29") (pintype "passive"))
    )
    (net (code "38") (name "/TDC_INT") (class "Default")
      (node (ref "DD1") (pin "8") (pinfunction "INTN_8") (pintype "passive"))
      (node (ref "DD2") (pin "31") (pinfunction "PA10_31") (pintype "passive"))
    )
    (net (code "39") (name "/TX") (class "Default")
      (node (ref "DD2") (pin "39") (pinfunction "PB3_39") (pintype "passive"))
      (node (ref "P10") (pin "1") (pinfunction "Pad_1") (pintype "passive"))
    )
    (net (code "40") (name "APD_V") (class "Default")
      (node (ref "C11") (pin "2") (pinfunction "2_2") (pintype "passive"))
      (node (ref "R1") (pin "2") (pinfunction "2_2") (pintype "passive"))
      (node (ref "R10") (pin "1") (pinfunction "1_1") (pintype "passive"))
    )
    (net (code "41") (name "GND") (class "Default")
      (node (ref "C1") (pin "1") (pinfunction "1_1") (pintype "passive"))
      (node (ref "C10") (pin "1") (pinfunction "1_1") (pintype "passive"))
      (node (ref "C11") (pin "1") (pinfunction "1_1") (pintype "passive"))
      (node (ref "C14") (pin "2") (pinfunction "2_2") (pintype "passive"))
      (node (ref "C15") (pin "2") (pinfunction "2_2") (pintype "passive"))
      (node (ref "C18") (pin "1") (pinfunction "1_1") (pintype "passive"))
      (node (ref "C20") (pin "1") (pinfunction "1_1") (pintype "passive"))
      (node (ref "C21") (pin "1") (pinfunction "1_1") (pintype "passive"))
      (node (ref "C22") (pin "1") (pinfunction "1_1") (pintype "passive"))
      (node (ref "C25") (pin "2") (pinfunction "2_2") (pintype "passive"))
      (node (ref "C26") (pin "1") (pinfunction "1_1") (pintype "passive"))
      (node (ref "C27") (pin "1") (pinfunction "1_1") (pintype "passive"))
      (node (ref "C28") (pin "2") (pinfunction "2_2") (pintype "passive"))
      (node (ref "C29") (pin "1") (pinfunction "1_1") (pintype "passive"))
      (node (ref "C3") (pin "1") (pinfunction "1_1") (pintype "passive"))
      (node (ref "C30") (pin "1") (pinfunction "1_1") (pintype "passive"))
      (node (ref "C31") (pin "1") (pinfunction "1_1") (pintype "passive"))
      (node (ref "C32") (pin "1") (pinfunction "1_1") (pintype "passive"))
      (node (ref "C33") (pin "1") (pinfunction "1_1") (pintype "passive"))
      (node (ref "C4") (pin "1") (pinfunction "1_1") (pintype "passive"))
      (node (ref "C5") (pin "1") (pinfunction "1_1") (pintype "passive"))
      (node (ref "C6") (pin "2") (pinfunction "2_2") (pintype "passive"))
      (node (ref "C7") (pin "1") (pinfunction "1_1") (pintype "passive"))
      (node (ref "C8") (pin "2") (pinfunction "2_2") (pintype "passive"))
      (node (ref "D6") (pin "1") (pinfunction "A_1") (pintype "passive"))
      (node (ref "DA2") (pin "1") (pinfunction "GND/ADJ_1") (pintype "power_in"))
      (node (ref "DA3") (pin "5") (pinfunction "GND_5") (pintype "power_in"))
      (node (ref "DA3") (pin "8") (pinfunction "GND_8") (pintype "power_in"))
      (node (ref "DA3") (pin "9") (pinfunction "GND_9") (pintype "power_in"))
      (node (ref "DA4") (pin "2") (pinfunction "V-_2") (pintype "power_in"))
      (node (ref "DD1") (pin "21") (pinfunction "GND_21") (pintype "passive"))
      (node (ref "DD1") (pin "28") (pinfunction "GND_28") (pintype "passive"))
      (node (ref "DD1") (pin "31") (pinfunction "START_31") (pintype "passive"))
      (node (ref "DD1") (pin "33") (pinfunction "PGND_33") (pintype "passive"))
      (node (ref "DD1") (pin "4") (pinfunction "GND_4") (pintype "passive"))
      (node (ref "DD2") (pin "23") (pinfunction "VSS_23") (pintype "passive"))
      (node (ref "DD2") (pin "35") (pinfunction "VSS_35") (pintype "passive"))
      (node (ref "DD2") (pin "44") (pinfunction "BOOT0_44") (pintype "passive"))
      (node (ref "DD2") (pin "47") (pinfunction "VSS_47") (pintype "passive"))
      (node (ref "DD2") (pin "8") (pinfunction "VSSA_8") (pintype "passive"))
      (node (ref "J1") (pin "G") (pinfunction "G_G") (pintype "passive"))
      (node (ref "LED1") (pin "2") (pinfunction "K_2") (pintype "passive"))
      (node (ref "P14") (pin "1") (pinfunction "Pad_1") (pintype "passive"))
      (node (ref "P2") (pin "1") (pinfunction "47_1") (pintype "passive"))
      (node (ref "P9") (pin "1") (pinfunction "Pad_1") (pintype "passive"))
      (node (ref "Q1") (pin "2") (pinfunction "SOURCE_2") (pintype "passive"))
      (node (ref "R14") (pin "1") (pinfunction "1_1") (pintype "passive"))
      (node (ref "R17") (pin "1") (pinfunction "1_1") (pintype "passive"))
      (node (ref "R29") (pin "1") (pinfunction "1_1") (pintype "passive"))
      (node (ref "R3") (pin "2") (pinfunction "2_2") (pintype "passive"))
      (node (ref "R9") (pin "2") (pinfunction "2_2") (pintype "passive"))
      (node (ref "W1") (pin "2") (pinfunction "2_2") (pintype "passive"))
      (node (ref "W2") (pin "2") (pinfunction "2_2") (pintype "passive"))
      (node (ref "W4") (pin "1") (pinfunction "1_1") (pintype "passive"))
      (node (ref "W5") (pin "1") (pinfunction "1_1") (pintype "passive"))
    )
    (net (code "42") (name "LGND") (class "Default")
      (node (ref "C16") (pin "1") (pinfunction "1_1") (pintype "passive"))
      (node (ref "C17") (pin "1") (pinfunction "1_1") (pintype "passive"))
      (node (ref "C19") (pin "1") (pinfunction "1_1") (pintype "passive"))
      (node (ref "C2") (pin "1") (pinfunction "1_1") (pintype "passive"))
      (node (ref "C23") (pin "1") (pinfunction "1_1") (pintype "passive"))
      (node (ref "C24") (pin "1") (pinfunction "1_1") (pintype "passive"))
      (node (ref "C9") (pin "1") (pinfunction "1_1") (pintype "passive"))
      (node (ref "DA1") (pin "2") (pinfunction "GND_2") (pintype "power_in"))
      (node (ref "DA5") (pin "2") (pinfunction "V-_2") (pintype "power_in"))
      (node (ref "DA6") (pin "4") (pinfunction "GND_4") (pintype "power_in"))
      (node (ref "DA6") (pin "5") (pinfunction "IN-_5") (pintype "input"))
      (node (ref "R16") (pin "1") (pinfunction "1_1") (pintype "passive"))
      (node (ref "R19") (pin "1") (pinfunction "1_1") (pintype "passive"))
      (node (ref "R23") (pin "2") (pinfunction "2_2") (pintype "passive"))
      (node (ref "R26") (pin "1") (pinfunction "1_1") (pintype "passive"))
      (node (ref "R6") (pin "1") (pinfunction "1_1") (pintype "passive"))
      (node (ref "W1") (pin "1") (pinfunction "1_1") (pintype "passive"))
      (node (ref "W2") (pin "1") (pinfunction "1_1") (pintype "passive"))
      (node (ref "W3") (pin "1") (pinfunction "1_1") (pintype "passive"))
    )
    (net (code "43") (name "MGND") (class "Default")
      (node (ref "C36") (pin "1") (pinfunction "1_1") (pintype "passive"))
      (node (ref "C37") (pin "2") (pinfunction "2_2") (pintype "passive"))
      (node (ref "C38") (pin "2") (pinfunction "2_2") (pintype "passive"))
      (node (ref "DA7") (pin "15") (pinfunction "FR_15") (pintype "passive"))
      (node (ref "DA7") (pin "17") (pinfunction "EP_17") (pintype "passive"))
      (node (ref "DA7") (pin "8") (pinfunction "GND_8") (pintype "passive"))
      (node (ref "R35") (pin "2") (pinfunction "2_2") (pintype "passive"))
      (node (ref "R37") (pin "2") (pinfunction "2_2") (pintype "passive"))
      (node (ref "R38") (pin "2") (pinfunction "2_2") (pintype "passive"))
      (node (ref "W4") (pin "2") (pinfunction "2_2") (pintype "passive"))
      (node (ref "W5") (pin "2") (pinfunction "2_2") (pintype "passive"))
    )
    (net (code "44") (name "Net-(C6-Pad1)") (class "Default")
      (node (ref "C6") (pin "1") (pinfunction "1_1") (pintype "passive"))
      (node (ref "L4") (pin "2") (pinfunction "2_2") (pintype "passive"))
      (node (ref "L5") (pin "1") (pinfunction "1_1") (pintype "passive"))
    )
    (net (code "45") (name "Net-(C14-Pad1)") (class "Default")
      (node (ref "C14") (pin "1") (pinfunction "1_1") (pintype "passive"))
      (node (ref "R12") (pin "1") (pinfunction "1_1") (pintype "passive"))
      (node (ref "R13") (pin "2") (pinfunction "2_2") (pintype "passive"))
    )
    (net (code "46") (name "Net-(C19-Pad2)") (class "Default")
      (node (ref "C19") (pin "2") (pinfunction "2_2") (pintype "passive"))
      (node (ref "L10") (pin "2") (pinfunction "2_2") (pintype "passive"))
      (node (ref "R22") (pin "1") (pinfunction "1_1") (pintype "passive"))
    )
    (net (code "47") (name "Net-(C20-Pad2)") (class "Default")
      (node (ref "C20") (pin "2") (pinfunction "2_2") (pintype "passive"))
      (node (ref "DD1") (pin "22") (pinfunction "VIO_22") (pintype "passive"))
      (node (ref "DD1") (pin "3") (pinfunction "VIO_3") (pintype "passive"))
      (node (ref "R21") (pin "2") (pinfunction "2_2") (pintype "passive"))
    )
    (net (code "48") (name "Net-(C33-Pad2)") (class "Default")
      (node (ref "C33") (pin "2") (pinfunction "2_2") (pintype "passive"))
      (node (ref "D3") (pin "C") (pinfunction "C_C") (pintype "passive"))
      (node (ref "R1") (pin "1") (pinfunction "1_1") (pintype "passive"))
    )
    (net (code "49") (name "Net-(D6-C)") (class "Default")
      (node (ref "D3") (pin "A") (pinfunction "A_A") (pintype "passive"))
      (node (ref "D6") (pin "3") (pinfunction "C_3") (pintype "passive"))
      (node (ref "DA3") (pin "2") (pinfunction "IN_2") (pintype "input"))
    )
    (net (code "50") (name "Net-(DA1-EN)") (class "Default")
      (node (ref "C2") (pin "2") (pinfunction "2_2") (pintype "passive"))
      (node (ref "DA1") (pin "4") (pinfunction "EN_4") (pintype "power_in"))
      (node (ref "DA1") (pin "5") (pinfunction "VIN_5") (pintype "passive"))
      (node (ref "L2") (pin "1") (pinfunction "1_1") (pintype "passive"))
      (node (ref "L3") (pin "1") (pinfunction "1_1") (pintype "passive"))
    )
    (net (code "51") (name "Net-(DA1-FB)") (class "Default")
      (node (ref "DA1") (pin "3") (pinfunction "FB_3") (pintype "power_in"))
      (node (ref "R4") (pin "2") (pinfunction "2_2") (pintype "passive"))
      (node (ref "R5") (pin "1") (pinfunction "1_1") (pintype "passive"))
      (node (ref "R6") (pin "2") (pinfunction "2_2") (pintype "passive"))
    )
    (net (code "52") (name "Net-(DA1-SW)") (class "Default")
      (node (ref "D2") (pin "A") (pinfunction "A_A") (pintype "passive"))
      (node (ref "DA1") (pin "1") (pinfunction "SW_1") (pintype "open_collector"))
      (node (ref "L3") (pin "2") (pinfunction "2_2") (pintype "passive"))
    )
    (net (code "53") (name "Net-(DA3-FILT)") (class "Default")
      (node (ref "C5") (pin "2") (pinfunction "2_2") (pintype "passive"))
      (node (ref "DA3") (pin "3") (pinfunction "FILT_3") (pintype "passive"))
    )
    (net (code "54") (name "Net-(DA4-V+)") (class "Default")
      (node (ref "C15") (pin "1") (pinfunction "1_1") (pintype "passive"))
      (node (ref "DA4") (pin "5") (pinfunction "V+_5") (pintype "power_in"))
      (node (ref "L7") (pin "2") (pinfunction "2_2") (pintype "passive"))
    )
    (net (code "55") (name "Net-(DA6-VDD)") (class "Default")
      (node (ref "C16") (pin "2") (pinfunction "2_2") (pintype "passive"))
      (node (ref "DA6") (pin "1") (pinfunction "VDD_1") (pintype "power_in"))
      (node (ref "L8") (pin "2") (pinfunction "2_2") (pintype "passive"))
    )
    (net (code "56") (name "Net-(DA7-CPN)") (class "Default")
      (node (ref "C34") (pin "2") (pinfunction "2_2") (pintype "passive"))
      (node (ref "DA7") (pin "6") (pinfunction "CPN_6") (pintype "passive"))
    )
    (net (code "57") (name "Net-(DA7-CPP)") (class "Default")
      (node (ref "C34") (pin "1") (pinfunction "1_1") (pintype "passive"))
      (node (ref "DA7") (pin "5") (pinfunction "CPP_5") (pintype "passive"))
    )
    (net (code "58") (name "Net-(DA7-CS)") (class "Default")
      (node (ref "DA7") (pin "14") (pinfunction "CS_14") (pintype "passive"))
      (node (ref "R37") (pin "1") (pinfunction "1_1") (pintype "passive"))
    )
    (net (code "59") (name "Net-(DA7-FS)") (class "Default")
      (node (ref "DA7") (pin "1") (pinfunction "FS_1") (pintype "passive"))
      (node (ref "R38") (pin "1") (pinfunction "1_1") (pintype "passive"))
    )
    (net (code "60") (name "Net-(DA7-V5)") (class "Default")
      (node (ref "C36") (pin "2") (pinfunction "2_2") (pintype "passive"))
      (node (ref "DA7") (pin "12") (pinfunction "V5_12") (pintype "passive"))
    )
    (net (code "61") (name "Net-(DA7-VCC)") (class "Default")
      (node (ref "C37") (pin "1") (pinfunction "1_1") (pintype "passive"))
      (node (ref "C38") (pin "1") (pinfunction "1_1") (pintype "passive"))
      (node (ref "DA7") (pin "11") (pinfunction "VCC_11") (pintype "passive"))
      (node (ref "L11") (pin "2") (pinfunction "2_2") (pintype "passive"))
    )
    (net (code "62") (name "Net-(DA7-VCP)") (class "Default")
      (node (ref "C35") (pin "2") (pinfunction "2_2") (pintype "passive"))
      (node (ref "DA7") (pin "4") (pinfunction "VCP_4") (pintype "passive"))
    )
    (net (code "63") (name "Net-(DD1-CLK32IN)") (class "Default")
      (node (ref "C22") (pin "2") (pinfunction "2_2") (pintype "passive"))
      (node (ref "DD1") (pin "16") (pinfunction "CLK32IN_16") (pintype "passive"))
      (node (ref "R24") (pin "1") (pinfunction "1_1") (pintype "passive"))
      (node (ref "X1") (pin "2") (pinfunction "2_2") (pintype "passive"))
    )
    (net (code "64") (name "Net-(DD1-CLK32OUT)") (class "Default")
      (node (ref "C21") (pin "2") (pinfunction "2_2") (pintype "passive"))
      (node (ref "DD1") (pin "15") (pinfunction "CLK32OUT_15") (pintype "passive"))
      (node (ref "R24") (pin "2") (pinfunction "2_2") (pintype "passive"))
      (node (ref "X1") (pin "1") (pinfunction "1_1") (pintype "passive"))
    )
    (net (code "65") (name "Net-(DD1-RSTN)") (class "Default")
      (node (ref "C29") (pin "2") (pinfunction "2_2") (pintype "passive"))
      (node (ref "DD1") (pin "13") (pinfunction "RSTN_13") (pintype "passive"))
      (node (ref "R31") (pin "2") (pinfunction "2_2") (pintype "passive"))
    )
    (net (code "66") (name "Net-(DD2-PA1)") (class "Default")
      (node (ref "DD2") (pin "11") (pinfunction "PA1_11") (pintype "passive"))
      (node (ref "P7") (pin "1") (pinfunction "Pad_1") (pintype "passive"))
    )
    (net (code "67") (name "Net-(DD2-PA2)") (class "Default")
      (node (ref "DD2") (pin "12") (pinfunction "PA2_12") (pintype "passive"))
      (node (ref "P8") (pin "1") (pinfunction "Pad_1") (pintype "passive"))
    )
    (net (code "68") (name "Net-(DD2-PF0{slash}OSC_IN)") (class "Default")
      (node (ref "C28") (pin "1") (pinfunction "1_1") (pintype "passive"))
      (node (ref "DD2") (pin "5") (pinfunction "PF0/OSC_IN_5") (pintype "passive"))
      (node (ref "X2") (pin "3") (pinfunction "3_3") (pintype "passive"))
    )
    (net (code "69") (name "Net-(DD2-PF0{slash}OSC_OUT)") (class "Default")
      (node (ref "C25") (pin "1") (pinfunction "1_1") (pintype "passive"))
      (node (ref "DD2") (pin "6") (pinfunction "PF0/OSC_OUT_6") (pintype "passive"))
      (node (ref "X2") (pin "1") (pinfunction "1_1") (pintype "passive"))
    )
    (net (code "70") (name "Net-(J1-PadS)") (class "Default")
      (node (ref "J1") (pin "S") (pinfunction "S_S") (pintype "passive"))
      (node (ref "R7") (pin "1") (pinfunction "1_1") (pintype "passive"))
    )
    (net (code "71") (name "Net-(J2-PadG)") (class "Default")
      (node (ref "J2") (pin "G") (pinfunction "G_G") (pintype "passive"))
      (node (ref "W3") (pin "2") (pinfunction "2_2") (pintype "passive"))
    )
    (net (code "72") (name "Net-(J2-PadS)") (class "Default")
      (node (ref "J2") (pin "S") (pinfunction "S_S") (pintype "passive"))
      (node (ref "R20") (pin "1") (pinfunction "1_1") (pintype "passive"))
    )
    (net (code "73") (name "Net-(L6-Pad2)") (class "Default")
      (node (ref "L6") (pin "2") (pinfunction "2_2") (pintype "passive"))
      (node (ref "R12") (pin "2") (pinfunction "2_2") (pintype "passive"))
    )
    (net (code "74") (name "Net-(L9-Pad1)") (class "Default")
      (node (ref "L9") (pin "1") (pinfunction "1_1") (pintype "passive"))
      (node (ref "R21") (pin "1") (pinfunction "1_1") (pintype "passive"))
      (node (ref "R30") (pin "1") (pinfunction "1_1") (pintype "passive"))
    )
    (net (code "75") (name "Net-(LED1-A)") (class "Default")
      (node (ref "LED1") (pin "1") (pinfunction "A_1") (pintype "passive"))
      (node (ref "R33") (pin "1") (pinfunction "1_1") (pintype "passive"))
    )
    (net (code "76") (name "Net-(P13-Pad)") (class "Default")
      (node (ref "P13") (pin "1") (pinfunction "Pad_1") (pintype "passive"))
      (node (ref "R36") (pin "2") (pinfunction "2_2") (pintype "passive"))
    )
    (net (code "77") (name "Net-(Q1-DRAIN)") (class "Default")
      (node (ref "D1") (pin "A") (pinfunction "A_A") (pintype "passive"))
      (node (ref "L5") (pin "2") (pinfunction "2_2") (pintype "passive"))
      (node (ref "Q1") (pin "3") (pinfunction "DRAIN_3") (pintype "passive"))
    )
    (net (code "78") (name "TDC_VCC") (class "Default")
      (node (ref "C18") (pin "2") (pinfunction "2_2") (pintype "passive"))
      (node (ref "DD1") (pin "14") (pinfunction "VCC_14") (pintype "passive"))
      (node (ref "DD1") (pin "25") (pinfunction "EN_STOP2_25") (pintype "passive"))
      (node (ref "DD1") (pin "26") (pinfunction "EN_STOP1_26") (pintype "passive"))
      (node (ref "DD1") (pin "29") (pinfunction "VCC_29") (pintype "passive"))
      (node (ref "R30") (pin "2") (pinfunction "2_2") (pintype "passive"))
      (node (ref "R31") (pin "1") (pinfunction "1_1") (pintype "passive"))
    )
    (net (code "79") (name "VCC") (class "Default")
      (node (ref "C24") (pin "2") (pinfunction "2_2") (pintype "passive"))
      (node (ref "C27") (pin "2") (pinfunction "2_2") (pintype "passive"))
      (node (ref "C30") (pin "2") (pinfunction "2_2") (pintype "passive"))
      (node (ref "C31") (pin "2") (pinfunction "2_2") (pintype "passive"))
      (node (ref "C32") (pin "2") (pinfunction "2_2") (pintype "passive"))
      (node (ref "C7") (pin "2") (pinfunction "2_2") (pintype "passive"))
      (node (ref "DA2") (pin "2") (pinfunction "VOUT_2") (pintype "power_in"))
      (node (ref "DA2") (pin "4") (pinfunction "VOUT_4") (pintype "power_in"))
      (node (ref "DA5") (pin "5") (pinfunction "V+_5") (pintype "power_in"))
      (node (ref "DD2") (pin "1") (pinfunction "VBAT_1") (pintype "passive"))
      (node (ref "DD2") (pin "24") (pinfunction "VDD_24") (pintype "passive"))
      (node (ref "DD2") (pin "36") (pinfunction "VDD_36") (pintype "passive"))
      (node (ref "DD2") (pin "48") (pinfunction "VDD_48") (pintype "passive"))
      (node (ref "DD2") (pin "9") (pinfunction "VDDA_9") (pintype "passive"))
      (node (ref "L1") (pin "1") (pinfunction "1_1") (pintype "passive"))
      (node (ref "L10") (pin "1") (pinfunction "1_1") (pintype "passive"))
      (node (ref "L7") (pin "1") (pinfunction "1_1") (pintype "passive"))
      (node (ref "L9") (pin "2") (pinfunction "2_2") (pintype "passive"))
      (node (ref "R25") (pin "1") (pinfunction "1_1") (pintype "passive"))
      (node (ref "R28") (pin "1") (pinfunction "1_1") (pintype "passive"))
      (node (ref "R34") (pin "1") (pinfunction "1_1") (pintype "passive"))
      (node (ref "R36") (pin "1") (pinfunction "1_1") (pintype "passive"))
    )
    (net (code "80") (name "VCC_TIA") (class "Default")
      (node (ref "C1") (pin "2") (pinfunction "2_2") (pintype "passive"))
      (node (ref "C4") (pin "2") (pinfunction "2_2") (pintype "passive"))
      (node (ref "D6") (pin "2") (pinfunction "K_2") (pintype "passive"))
      (node (ref "DA3") (pin "1") (pinfunction "VCC_1") (pintype "power_in"))
      (node (ref "L1") (pin "2") (pinfunction "2_2") (pintype "passive"))
    )
    (net (code "81") (name "Vin") (class "Default")
      (node (ref "C3") (pin "2") (pinfunction "2_2") (pintype "passive"))
      (node (ref "C35") (pin "1") (pinfunction "1_1") (pintype "passive"))
      (node (ref "DA2") (pin "3") (pinfunction "VIN_3") (pintype "power_in"))
      (node (ref "L11") (pin "1") (pinfunction "1_1") (pintype "passive"))
      (node (ref "L2") (pin "2") (pinfunction "2_2") (pintype "passive"))
      (node (ref "L4") (pin "1") (pinfunction "1_1") (pintype "passive"))
      (node (ref "P1") (pin "1") (pinfunction "47_1") (pintype "passive"))
    )
    (net (code "82") (name "Vlaser") (class "Default")
      (node (ref "C9") (pin "2") (pinfunction "2_2") (pintype "passive"))
      (node (ref "D2") (pin "K") (pinfunction "K_K") (pintype "passive"))
      (node (ref "L8") (pin "1") (pinfunction "1_1") (pintype "passive"))
      (node (ref "R18") (pin "2") (pinfunction "2_2") (pintype "passive"))
      (node (ref "R5") (pin "2") (pinfunction "2_2") (pintype "passive"))
    )
    (net (code "83") (name "unconnected-(DA3-MON-Pad4)") (class "Default")
      (node (ref "DA3") (pin "4") (pinfunction "MON_4") (pintype "passive"))
    )
    (net (code "84") (name "unconnected-(DA7-FG-Pad2)") (class "Default")
      (node (ref "DA7") (pin "2") (pinfunction "FG_2") (pintype "passive"))
    )
    (net (code "85") (name "unconnected-(DA7-RD-Pad3)") (class "Default")
      (node (ref "DA7") (pin "3") (pinfunction "RD_3") (pintype "passive"))
    )
    (net (code "86") (name "unconnected-(DD1-EN_START-Pad32)") (class "Default")
      (node (ref "DD1") (pin "32") (pinfunction "EN_START_32") (pintype "passive"))
    )
    (net (code "87") (name "unconnected-(DD1-FIRE_DOWN-Pad6)") (class "Default")
      (node (ref "DD1") (pin "6") (pinfunction "FIRE_DOWN_6") (pintype "passive"))
    )
    (net (code "88") (name "unconnected-(DD1-FIRE_IN-Pad7)") (class "Default")
      (node (ref "DD1") (pin "7") (pinfunction "FIRE_IN_7") (pintype "passive"))
    )
    (net (code "89") (name "unconnected-(DD1-LOADT-Pad18)") (class "Default")
      (node (ref "DD1") (pin "18") (pinfunction "LOADT_18") (pintype "passive"))
    )
    (net (code "90") (name "unconnected-(DD1-PT1-Pad24)") (class "Default")
      (node (ref "DD1") (pin "24") (pinfunction "PT1_24") (pintype "passive"))
    )
    (net (code "91") (name "unconnected-(DD1-PT2-Pad23)") (class "Default")
      (node (ref "DD1") (pin "23") (pinfunction "PT2_23") (pintype "passive"))
    )
    (net (code "92") (name "unconnected-(DD1-PT3-Pad20)") (class "Default")
      (node (ref "DD1") (pin "20") (pinfunction "PT3_20") (pintype "passive"))
    )
    (net (code "93") (name "unconnected-(DD1-PT4-Pad19)") (class "Default")
      (node (ref "DD1") (pin "19") (pinfunction "PT4_19") (pintype "passive"))
    )
    (net (code "94") (name "unconnected-(DD1-SENSET-Pad17)") (class "Default")
      (node (ref "DD1") (pin "17") (pinfunction "SENSET_17") (pintype "passive"))
    )
    (net (code "95") (name "unconnected-(DD1-XOUT-Pad2)") (class "Default")
      (node (ref "DD1") (pin "2") (pinfunction "XOUT_2") (pintype "passive"))
    )
    (net (code "96") (name "unconnected-(DD2-PA6-Pad16)") (class "Default")
      (node (ref "DD2") (pin "16") (pinfunction "PA6_16") (pintype "passive"))
    )
    (net (code "97") (name "unconnected-(DD2-PA11-Pad32)") (class "Default")
      (node (ref "DD2") (pin "32") (pinfunction "PA11_32") (pintype "passive"))
    )
    (net (code "98") (name "unconnected-(DD2-PA15-Pad38)") (class "Default")
      (node (ref "DD2") (pin "38") (pinfunction "PA15_38") (pintype "passive"))
    )
    (net (code "99") (name "unconnected-(DD2-PB0-Pad18)") (class "Default")
      (node (ref "DD2") (pin "18") (pinfunction "PB0_18") (pintype "passive"))
    )
    (net (code "100") (name "unconnected-(DD2-PB1-Pad19)") (class "Default")
      (node (ref "DD2") (pin "19") (pinfunction "PB1_19") (pintype "passive"))
    )
    (net (code "101") (name "unconnected-(DD2-PB5-Pad41)") (class "Default")
      (node (ref "DD2") (pin "41") (pinfunction "PB5_41") (pintype "passive"))
    )
    (net (code "102") (name "unconnected-(DD2-PB6-Pad42)") (class "Default")
      (node (ref "DD2") (pin "42") (pinfunction "PB6_42") (pintype "passive"))
    )
    (net (code "103") (name "unconnected-(DD2-PB7-Pad43)") (class "Default")
      (node (ref "DD2") (pin "43") (pinfunction "PB7_43") (pintype "passive"))
    )
    (net (code "104") (name "unconnected-(DD2-PB8-Pad45)") (class "Default")
      (node (ref "DD2") (pin "45") (pinfunction "PB8_45") (pintype "passive"))
    )
    (net (code "105") (name "unconnected-(DD2-PB9-Pad46)") (class "Default")
      (node (ref "DD2") (pin "46") (pinfunction "PB9_46") (pintype "passive"))
    )
    (net (code "106") (name "unconnected-(DD2-PB11-Pad22)") (class "Default")
      (node (ref "DD2") (pin "22") (pinfunction "PB11_22") (pintype "passive"))
    )
    (net (code "107") (name "unconnected-(DD2-PC13-Pad2)") (class "Default")
      (node (ref "DD2") (pin "2") (pinfunction "PC13_2") (pintype "passive"))
    )
    (net (code "108") (name "unconnected-(DD2-PC14-Pad3)") (class "Default")
      (node (ref "DD2") (pin "3") (pinfunction "PC14_3") (pintype "passive"))
    )
    (net (code "109") (name "unconnected-(DD2-PC15-Pad4)") (class "Default")
      (node (ref "DD2") (pin "4") (pinfunction "PC15_4") (pintype "passive"))
    )
  )
)
